# B165X.net
KiCad netlist of a schematic drawn in EAGLE
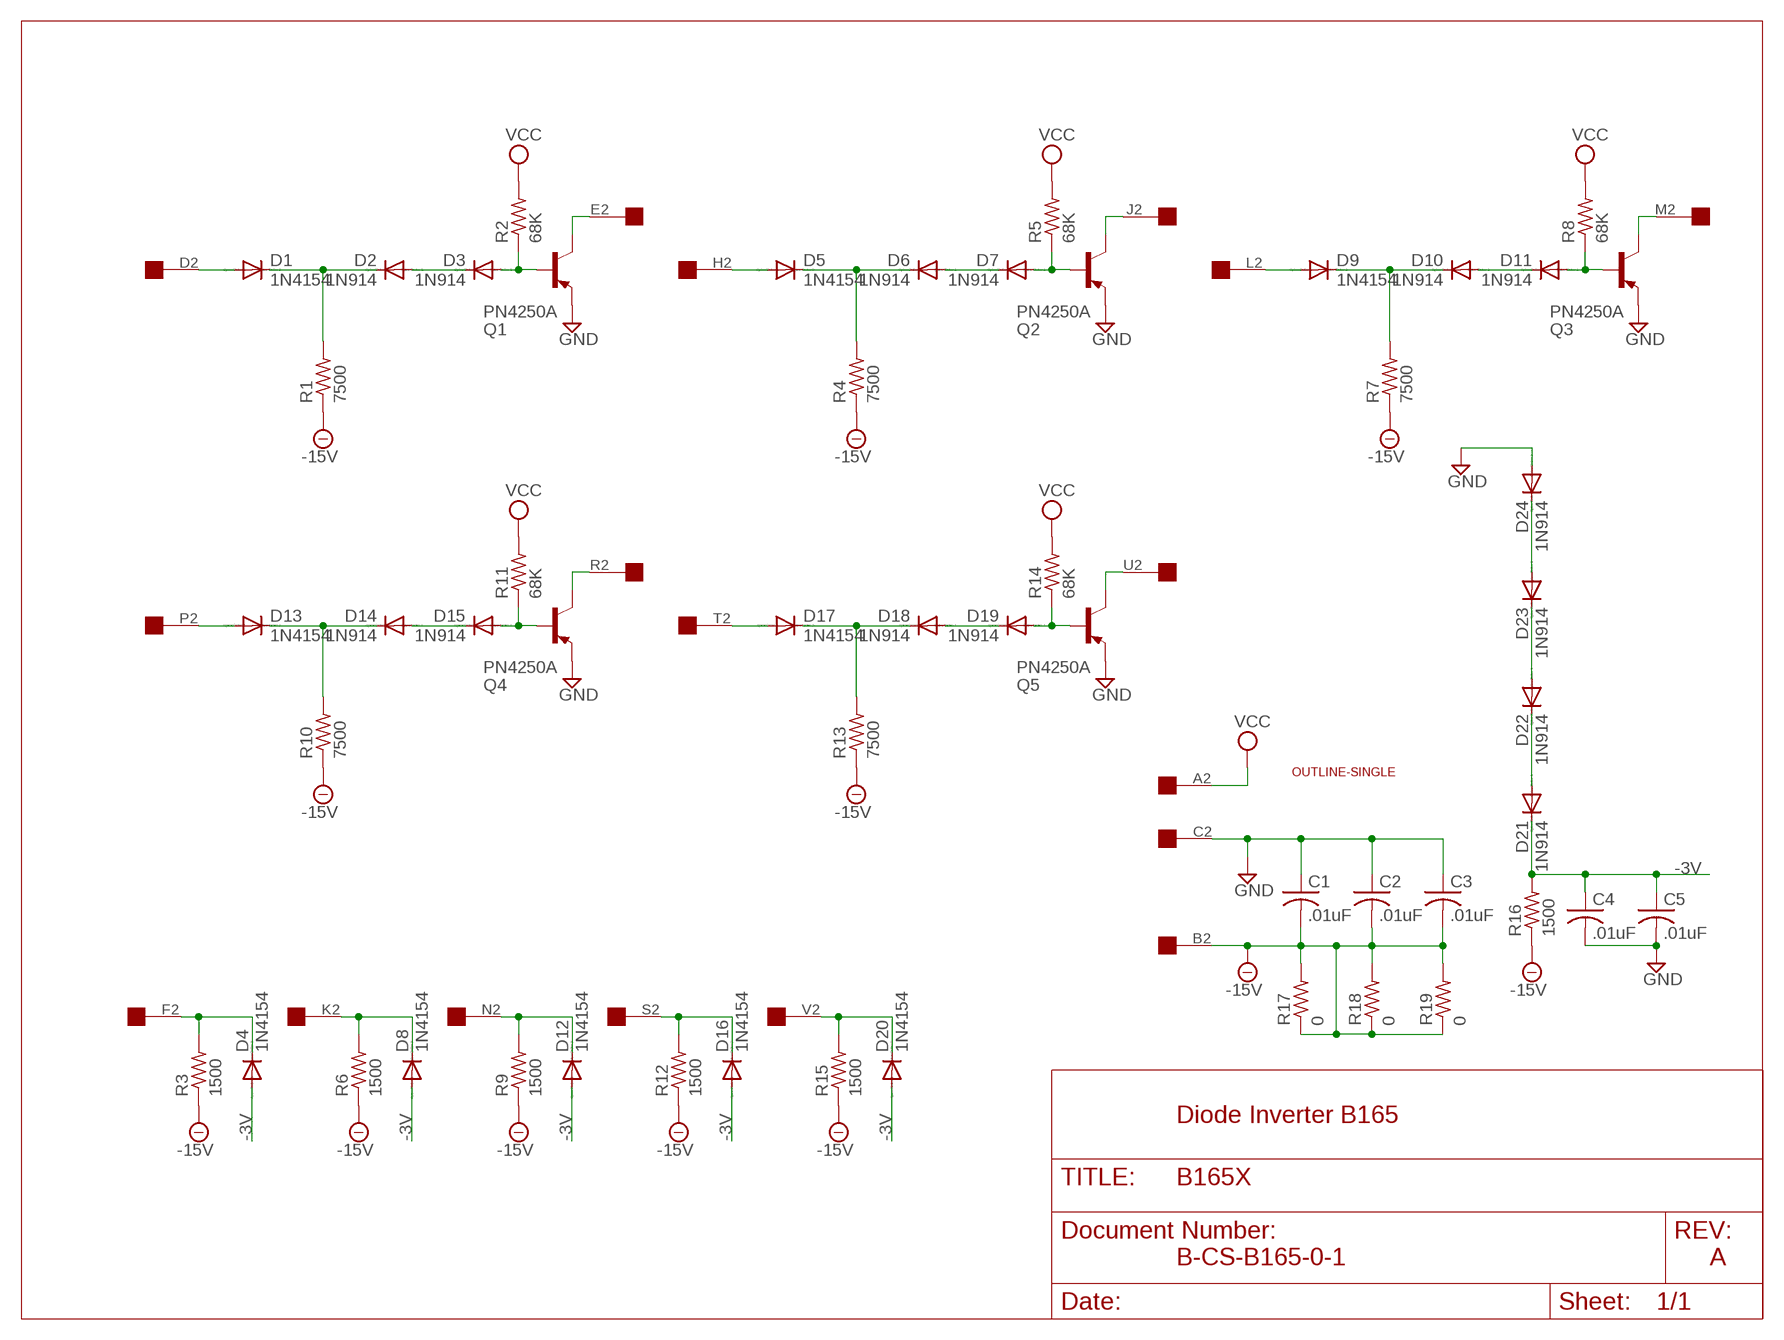
[diagram p0: schematic, sheet 1]

(export (version "E")
  (design (tool "Eeschema 10.0.6"))
  (components
    (comp (ref "C1")
      (value ".01uF")
      (footprint "eagle-import:C063-025X075")
      (libsource (lib "eagle-import") (part "C-US"))
    )
    (comp (ref "C2")
      (value ".01uF")
      (footprint "eagle-import:C063-025X075")
      (libsource (lib "eagle-import") (part "C-US"))
    )
    (comp (ref "C3")
      (value ".01uF")
      (footprint "eagle-import:C063-025X075")
      (libsource (lib "eagle-import") (part "C-US"))
    )
    (comp (ref "C4")
      (value ".01uF")
      (footprint "eagle-import:C063-025X075")
      (libsource (lib "eagle-import") (part "C-US"))
    )
    (comp (ref "C5")
      (value ".01uF")
      (footprint "eagle-import:C063-025X075")
      (libsource (lib "eagle-import") (part "C-US"))
    )
    (comp (ref "D1")
      (value "1N4154")
      (footprint "eagle-import:DO35-10")
      (libsource (lib "eagle-import") (part "DIODE-DO35-10"))
    )
    (comp (ref "D2")
      (value "1N914")
      (footprint "eagle-import:DO35-10")
      (libsource (lib "eagle-import") (part "DIODE-DO35-10"))
    )
    (comp (ref "D3")
      (value "1N914")
      (footprint "eagle-import:DO35-10")
      (libsource (lib "eagle-import") (part "DIODE-DO35-10"))
    )
    (comp (ref "D4")
      (value "1N4154")
      (footprint "eagle-import:DO35-10")
      (libsource (lib "eagle-import") (part "DIODE-DO35-10"))
    )
    (comp (ref "D5")
      (value "1N4154")
      (footprint "eagle-import:DO35-10")
      (libsource (lib "eagle-import") (part "DIODE-DO35-10"))
    )
    (comp (ref "D6")
      (value "1N914")
      (footprint "eagle-import:DO35-10")
      (libsource (lib "eagle-import") (part "DIODE-DO35-10"))
    )
    (comp (ref "D7")
      (value "1N914")
      (footprint "eagle-import:DO35-10")
      (libsource (lib "eagle-import") (part "DIODE-DO35-10"))
    )
    (comp (ref "D8")
      (value "1N4154")
      (footprint "eagle-import:DO35-10")
      (libsource (lib "eagle-import") (part "DIODE-DO35-10"))
    )
    (comp (ref "D9")
      (value "1N4154")
      (footprint "eagle-import:DO35-10")
      (libsource (lib "eagle-import") (part "DIODE-DO35-10"))
    )
    (comp (ref "D10")
      (value "1N914")
      (footprint "eagle-import:DO35-10")
      (libsource (lib "eagle-import") (part "DIODE-DO35-10"))
    )
    (comp (ref "D11")
      (value "1N914")
      (footprint "eagle-import:DO35-10")
      (libsource (lib "eagle-import") (part "DIODE-DO35-10"))
    )
    (comp (ref "D12")
      (value "1N4154")
      (footprint "eagle-import:DO35-10")
      (libsource (lib "eagle-import") (part "DIODE-DO35-10"))
    )
    (comp (ref "D13")
      (value "1N4154")
      (footprint "eagle-import:DO35-10")
      (libsource (lib "eagle-import") (part "DIODE-DO35-10"))
    )
    (comp (ref "D14")
      (value "1N914")
      (footprint "eagle-import:DO35-10")
      (libsource (lib "eagle-import") (part "DIODE-DO35-10"))
    )
    (comp (ref "D15")
      (value "1N914")
      (footprint "eagle-import:DO35-10")
      (libsource (lib "eagle-import") (part "DIODE-DO35-10"))
    )
    (comp (ref "D16")
      (value "1N4154")
      (footprint "eagle-import:DO35-10")
      (libsource (lib "eagle-import") (part "DIODE-DO35-10"))
    )
    (comp (ref "D17")
      (value "1N4154")
      (footprint "eagle-import:DO35-10")
      (libsource (lib "eagle-import") (part "DIODE-DO35-10"))
    )
    (comp (ref "D18")
      (value "1N914")
      (footprint "eagle-import:DO35-10")
      (libsource (lib "eagle-import") (part "DIODE-DO35-10"))
    )
    (comp (ref "D19")
      (value "1N914")
      (footprint "eagle-import:DO35-10")
      (libsource (lib "eagle-import") (part "DIODE-DO35-10"))
    )
    (comp (ref "D20")
      (value "1N4154")
      (footprint "eagle-import:DO35-10")
      (libsource (lib "eagle-import") (part "DIODE-DO35-10"))
    )
    (comp (ref "D21")
      (value "1N914")
      (footprint "eagle-import:DO35-10")
      (libsource (lib "eagle-import") (part "DIODE-DO35-10"))
    )
    (comp (ref "D22")
      (value "1N914")
      (footprint "eagle-import:DO35-10")
      (libsource (lib "eagle-import") (part "DIODE-DO35-10"))
    )
    (comp (ref "D23")
      (value "1N914")
      (footprint "eagle-import:DO35-10")
      (libsource (lib "eagle-import") (part "DIODE-DO35-10"))
    )
    (comp (ref "D24")
      (value "1N914")
      (footprint "eagle-import:DO35-10")
      (libsource (lib "eagle-import") (part "DIODE-DO35-10"))
    )
    (comp (ref "Q1")
      (value "PN4250A")
      (footprint "eagle-import:TO5")
      (libsource (lib "eagle-import") (part "-PNP-TO5"))
    )
    (comp (ref "Q2")
      (value "PN4250A")
      (footprint "eagle-import:TO5")
      (libsource (lib "eagle-import") (part "-PNP-TO5"))
    )
    (comp (ref "Q3")
      (value "PN4250A")
      (footprint "eagle-import:TO5")
      (libsource (lib "eagle-import") (part "-PNP-TO5"))
    )
    (comp (ref "Q4")
      (value "PN4250A")
      (footprint "eagle-import:TO5")
      (libsource (lib "eagle-import") (part "-PNP-TO5"))
    )
    (comp (ref "Q5")
      (value "PN4250A")
      (footprint "eagle-import:TO5")
      (libsource (lib "eagle-import") (part "-PNP-TO5"))
    )
    (comp (ref "R1")
      (value "7500")
      (footprint "eagle-import:0207_10")
      (libsource (lib "eagle-import") (part "R-US_0207/10"))
    )
    (comp (ref "R2")
      (value "68K")
      (footprint "eagle-import:0207_10")
      (libsource (lib "eagle-import") (part "R-US_0207/10"))
    )
    (comp (ref "R3")
      (value "1500")
      (footprint "eagle-import:0207_10")
      (libsource (lib "eagle-import") (part "R-US_0207/10"))
    )
    (comp (ref "R4")
      (value "7500")
      (footprint "eagle-import:0207_10")
      (libsource (lib "eagle-import") (part "R-US_0207/10"))
    )
    (comp (ref "R5")
      (value "68K")
      (footprint "eagle-import:0207_10")
      (libsource (lib "eagle-import") (part "R-US_0207/10"))
    )
    (comp (ref "R6")
      (value "1500")
      (footprint "eagle-import:0207_10")
      (libsource (lib "eagle-import") (part "R-US_0207/10"))
    )
    (comp (ref "R7")
      (value "7500")
      (footprint "eagle-import:0207_10")
      (libsource (lib "eagle-import") (part "R-US_0207/10"))
    )
    (comp (ref "R8")
      (value "68K")
      (footprint "eagle-import:0207_10")
      (libsource (lib "eagle-import") (part "R-US_0207/10"))
    )
    (comp (ref "R9")
      (value "1500")
      (footprint "eagle-import:0207_10")
      (libsource (lib "eagle-import") (part "R-US_0207/10"))
    )
    (comp (ref "R10")
      (value "7500")
      (footprint "eagle-import:0207_10")
      (libsource (lib "eagle-import") (part "R-US_0207/10"))
    )
    (comp (ref "R11")
      (value "68K")
      (footprint "eagle-import:0207_10")
      (libsource (lib "eagle-import") (part "R-US_0207/10"))
    )
    (comp (ref "R12")
      (value "1500")
      (footprint "eagle-import:0207_10")
      (libsource (lib "eagle-import") (part "R-US_0207/10"))
    )
    (comp (ref "R13")
      (value "7500")
      (footprint "eagle-import:0207_10")
      (libsource (lib "eagle-import") (part "R-US_0207/10"))
    )
    (comp (ref "R14")
      (value "68K")
      (footprint "eagle-import:0207_10")
      (libsource (lib "eagle-import") (part "R-US_0207/10"))
    )
    (comp (ref "R15")
      (value "1500")
      (footprint "eagle-import:0207_10")
      (libsource (lib "eagle-import") (part "R-US_0207/10"))
    )
    (comp (ref "R16")
      (value "1500")
      (footprint "eagle-import:0207_10")
      (libsource (lib "eagle-import") (part "R-US_0207/10"))
    )
    (comp (ref "R17")
      (value "0")
      (footprint "eagle-import:0207_10")
      (libsource (lib "eagle-import") (part "R-US_0207/10"))
    )
    (comp (ref "R18")
      (value "0")
      (footprint "eagle-import:0207_10")
      (libsource (lib "eagle-import") (part "R-US_0207/10"))
    )
    (comp (ref "R19")
      (value "0")
      (footprint "eagle-import:0207_10")
      (libsource (lib "eagle-import") (part "R-US_0207/10"))
    )
    (comp (ref "U$1")
      (value "OUTLINE-SINGLE")
      (footprint "eagle-import:SINGLE")
      (libsource (lib "eagle-import") (part "OUTLINE-SINGLE"))
    )
    (comp (ref "U$2")
      (value "EDGE-1")
      (footprint "eagle-import:EDGE-CON1")
      (libsource (lib "eagle-import") (part "EDGE-1"))
    )
  )
  (nets
    (net (code "1") (name "-15V") (class "Default")
      (node (ref "C1") (pin "2") (pinfunction "2_2") (pintype "passive"))
      (node (ref "C2") (pin "2") (pinfunction "2_2") (pintype "passive"))
      (node (ref "C3") (pin "2") (pinfunction "2_2") (pintype "passive"))
      (node (ref "R1") (pin "1") (pinfunction "1_1") (pintype "passive"))
      (node (ref "R10") (pin "1") (pinfunction "1_1") (pintype "passive"))
      (node (ref "R12") (pin "1") (pinfunction "1_1") (pintype "passive"))
      (node (ref "R13") (pin "1") (pinfunction "1_1") (pintype "passive"))
      (node (ref "R15") (pin "1") (pinfunction "1_1") (pintype "passive"))
      (node (ref "R16") (pin "1") (pinfunction "1_1") (pintype "passive"))
      (node (ref "R17") (pin "1") (pinfunction "1_1") (pintype "passive"))
      (node (ref "R17") (pin "2") (pinfunction "2_2") (pintype "passive"))
      (node (ref "R18") (pin "1") (pinfunction "1_1") (pintype "passive"))
      (node (ref "R18") (pin "2") (pinfunction "2_2") (pintype "passive"))
      (node (ref "R19") (pin "1") (pinfunction "1_1") (pintype "passive"))
      (node (ref "R19") (pin "2") (pinfunction "2_2") (pintype "passive"))
      (node (ref "R3") (pin "1") (pinfunction "1_1") (pintype "passive"))
      (node (ref "R4") (pin "1") (pinfunction "1_1") (pintype "passive"))
      (node (ref "R6") (pin "1") (pinfunction "1_1") (pintype "passive"))
      (node (ref "R7") (pin "1") (pinfunction "1_1") (pintype "passive"))
      (node (ref "R9") (pin "1") (pinfunction "1_1") (pintype "passive"))
      (node (ref "U$2") (pin "B2") (pinfunction "1_B2") (pintype "bidirectional"))
    )
    (net (code "2") (name "/-3V") (class "Default")
      (node (ref "C4") (pin "1") (pinfunction "1_1") (pintype "passive"))
      (node (ref "C5") (pin "1") (pinfunction "1_1") (pintype "passive"))
      (node (ref "D12") (pin "A") (pinfunction "A_A") (pintype "passive"))
      (node (ref "D16") (pin "A") (pinfunction "A_A") (pintype "passive"))
      (node (ref "D20") (pin "A") (pinfunction "A_A") (pintype "passive"))
      (node (ref "D21") (pin "C") (pinfunction "C_C") (pintype "passive"))
      (node (ref "D4") (pin "A") (pinfunction "A_A") (pintype "passive"))
      (node (ref "D8") (pin "A") (pinfunction "A_A") (pintype "passive"))
      (node (ref "R16") (pin "2") (pinfunction "2_2") (pintype "passive"))
    )
    (net (code "3") (name "GND") (class "Default")
      (node (ref "C1") (pin "1") (pinfunction "1_1") (pintype "passive"))
      (node (ref "C2") (pin "1") (pinfunction "1_1") (pintype "passive"))
      (node (ref "C3") (pin "1") (pinfunction "1_1") (pintype "passive"))
      (node (ref "C4") (pin "2") (pinfunction "2_2") (pintype "passive"))
      (node (ref "C5") (pin "2") (pinfunction "2_2") (pintype "passive"))
      (node (ref "D24") (pin "A") (pinfunction "A_A") (pintype "passive"))
      (node (ref "Q1") (pin "1") (pinfunction "E_1") (pintype "passive"))
      (node (ref "Q2") (pin "1") (pinfunction "E_1") (pintype "passive"))
      (node (ref "Q3") (pin "1") (pinfunction "E_1") (pintype "passive"))
      (node (ref "Q4") (pin "1") (pinfunction "E_1") (pintype "passive"))
      (node (ref "Q5") (pin "1") (pinfunction "E_1") (pintype "passive"))
      (node (ref "U$2") (pin "C2") (pinfunction "1_C2") (pintype "bidirectional"))
    )
    (net (code "4") (name "Net-(D1-PadC)") (class "Default")
      (node (ref "D1") (pin "C") (pinfunction "C_C") (pintype "passive"))
      (node (ref "D2") (pin "C") (pinfunction "C_C") (pintype "passive"))
      (node (ref "R1") (pin "2") (pinfunction "2_2") (pintype "passive"))
    )
    (net (code "5") (name "Net-(D2-PadA)") (class "Default")
      (node (ref "D2") (pin "A") (pinfunction "A_A") (pintype "passive"))
      (node (ref "D3") (pin "C") (pinfunction "C_C") (pintype "passive"))
    )
    (net (code "6") (name "Net-(D5-PadC)") (class "Default")
      (node (ref "D5") (pin "C") (pinfunction "C_C") (pintype "passive"))
      (node (ref "D6") (pin "C") (pinfunction "C_C") (pintype "passive"))
      (node (ref "R4") (pin "2") (pinfunction "2_2") (pintype "passive"))
    )
    (net (code "7") (name "Net-(D6-PadA)") (class "Default")
      (node (ref "D6") (pin "A") (pinfunction "A_A") (pintype "passive"))
      (node (ref "D7") (pin "C") (pinfunction "C_C") (pintype "passive"))
    )
    (net (code "8") (name "Net-(D10-PadA)") (class "Default")
      (node (ref "D10") (pin "A") (pinfunction "A_A") (pintype "passive"))
      (node (ref "D11") (pin "C") (pinfunction "C_C") (pintype "passive"))
    )
    (net (code "9") (name "Net-(D10-PadC)") (class "Default")
      (node (ref "D10") (pin "C") (pinfunction "C_C") (pintype "passive"))
      (node (ref "D9") (pin "C") (pinfunction "C_C") (pintype "passive"))
      (node (ref "R7") (pin "2") (pinfunction "2_2") (pintype "passive"))
    )
    (net (code "10") (name "Net-(D13-PadC)") (class "Default")
      (node (ref "D13") (pin "C") (pinfunction "C_C") (pintype "passive"))
      (node (ref "D14") (pin "C") (pinfunction "C_C") (pintype "passive"))
      (node (ref "R10") (pin "2") (pinfunction "2_2") (pintype "passive"))
    )
    (net (code "11") (name "Net-(D14-PadA)") (class "Default")
      (node (ref "D14") (pin "A") (pinfunction "A_A") (pintype "passive"))
      (node (ref "D15") (pin "C") (pinfunction "C_C") (pintype "passive"))
    )
    (net (code "12") (name "Net-(D17-PadC)") (class "Default")
      (node (ref "D17") (pin "C") (pinfunction "C_C") (pintype "passive"))
      (node (ref "D18") (pin "C") (pinfunction "C_C") (pintype "passive"))
      (node (ref "R13") (pin "2") (pinfunction "2_2") (pintype "passive"))
    )
    (net (code "13") (name "Net-(D18-PadA)") (class "Default")
      (node (ref "D18") (pin "A") (pinfunction "A_A") (pintype "passive"))
      (node (ref "D19") (pin "C") (pinfunction "C_C") (pintype "passive"))
    )
    (net (code "14") (name "Net-(D21-PadA)") (class "Default")
      (node (ref "D21") (pin "A") (pinfunction "A_A") (pintype "passive"))
      (node (ref "D22") (pin "C") (pinfunction "C_C") (pintype "passive"))
    )
    (net (code "15") (name "Net-(D22-PadA)") (class "Default")
      (node (ref "D22") (pin "A") (pinfunction "A_A") (pintype "passive"))
      (node (ref "D23") (pin "C") (pinfunction "C_C") (pintype "passive"))
    )
    (net (code "16") (name "Net-(D23-PadA)") (class "Default")
      (node (ref "D23") (pin "A") (pinfunction "A_A") (pintype "passive"))
      (node (ref "D24") (pin "C") (pinfunction "C_C") (pintype "passive"))
    )
    (net (code "17") (name "Net-(Q1-B)") (class "Default")
      (node (ref "D3") (pin "A") (pinfunction "A_A") (pintype "passive"))
      (node (ref "Q1") (pin "2") (pinfunction "B_2") (pintype "passive"))
      (node (ref "R2") (pin "1") (pinfunction "1_1") (pintype "passive"))
    )
    (net (code "18") (name "Net-(Q1-C)") (class "Default")
      (node (ref "Q1") (pin "3") (pinfunction "C_3") (pintype "passive"))
      (node (ref "U$2") (pin "E2") (pinfunction "1_E2") (pintype "bidirectional"))
    )
    (net (code "19") (name "Net-(Q2-B)") (class "Default")
      (node (ref "D7") (pin "A") (pinfunction "A_A") (pintype "passive"))
      (node (ref "Q2") (pin "2") (pinfunction "B_2") (pintype "passive"))
      (node (ref "R5") (pin "1") (pinfunction "1_1") (pintype "passive"))
    )
    (net (code "20") (name "Net-(Q2-C)") (class "Default")
      (node (ref "Q2") (pin "3") (pinfunction "C_3") (pintype "passive"))
      (node (ref "U$2") (pin "J2") (pinfunction "1_J2") (pintype "bidirectional"))
    )
    (net (code "21") (name "Net-(Q3-B)") (class "Default")
      (node (ref "D11") (pin "A") (pinfunction "A_A") (pintype "passive"))
      (node (ref "Q3") (pin "2") (pinfunction "B_2") (pintype "passive"))
      (node (ref "R8") (pin "1") (pinfunction "1_1") (pintype "passive"))
    )
    (net (code "22") (name "Net-(Q3-C)") (class "Default")
      (node (ref "Q3") (pin "3") (pinfunction "C_3") (pintype "passive"))
      (node (ref "U$2") (pin "M2") (pinfunction "1_M2") (pintype "bidirectional"))
    )
    (net (code "23") (name "Net-(Q4-B)") (class "Default")
      (node (ref "D15") (pin "A") (pinfunction "A_A") (pintype "passive"))
      (node (ref "Q4") (pin "2") (pinfunction "B_2") (pintype "passive"))
      (node (ref "R11") (pin "1") (pinfunction "1_1") (pintype "passive"))
    )
    (net (code "24") (name "Net-(Q4-C)") (class "Default")
      (node (ref "Q4") (pin "3") (pinfunction "C_3") (pintype "passive"))
      (node (ref "U$2") (pin "R2") (pinfunction "1_R2") (pintype "bidirectional"))
    )
    (net (code "25") (name "Net-(Q5-B)") (class "Default")
      (node (ref "D19") (pin "A") (pinfunction "A_A") (pintype "passive"))
      (node (ref "Q5") (pin "2") (pinfunction "B_2") (pintype "passive"))
      (node (ref "R14") (pin "1") (pinfunction "1_1") (pintype "passive"))
    )
    (net (code "26") (name "Net-(Q5-C)") (class "Default")
      (node (ref "Q5") (pin "3") (pinfunction "C_3") (pintype "passive"))
      (node (ref "U$2") (pin "U2") (pinfunction "1_U2") (pintype "bidirectional"))
    )
    (net (code "27") (name "Net-(U$2D-1)") (class "Default")
      (node (ref "D1") (pin "A") (pinfunction "A_A") (pintype "passive"))
      (node (ref "U$2") (pin "D2") (pinfunction "1_D2") (pintype "bidirectional"))
    )
    (net (code "28") (name "Net-(U$2F-1)") (class "Default")
      (node (ref "D4") (pin "C") (pinfunction "C_C") (pintype "passive"))
      (node (ref "R3") (pin "2") (pinfunction "2_2") (pintype "passive"))
      (node (ref "U$2") (pin "F2") (pinfunction "1_F2") (pintype "bidirectional"))
    )
    (net (code "29") (name "Net-(U$2G-1)") (class "Default")
      (node (ref "D5") (pin "A") (pinfunction "A_A") (pintype "passive"))
      (node (ref "U$2") (pin "H2") (pinfunction "1_H2") (pintype "bidirectional"))
    )
    (net (code "30") (name "Net-(U$2I-1)") (class "Default")
      (node (ref "D8") (pin "C") (pinfunction "C_C") (pintype "passive"))
      (node (ref "R6") (pin "2") (pinfunction "2_2") (pintype "passive"))
      (node (ref "U$2") (pin "K2") (pinfunction "1_K2") (pintype "bidirectional"))
    )
    (net (code "31") (name "Net-(U$2J-1)") (class "Default")
      (node (ref "D9") (pin "A") (pinfunction "A_A") (pintype "passive"))
      (node (ref "U$2") (pin "L2") (pinfunction "1_L2") (pintype "bidirectional"))
    )
    (net (code "32") (name "Net-(U$2L-1)") (class "Default")
      (node (ref "D12") (pin "C") (pinfunction "C_C") (pintype "passive"))
      (node (ref "R9") (pin "2") (pinfunction "2_2") (pintype "passive"))
      (node (ref "U$2") (pin "N2") (pinfunction "1_N2") (pintype "bidirectional"))
    )
    (net (code "33") (name "Net-(U$2M-1)") (class "Default")
      (node (ref "D13") (pin "A") (pinfunction "A_A") (pintype "passive"))
      (node (ref "U$2") (pin "P2") (pinfunction "1_P2") (pintype "bidirectional"))
    )
    (net (code "34") (name "Net-(U$2O-1)") (class "Default")
      (node (ref "D16") (pin "C") (pinfunction "C_C") (pintype "passive"))
      (node (ref "R12") (pin "2") (pinfunction "2_2") (pintype "passive"))
      (node (ref "U$2") (pin "S2") (pinfunction "1_S2") (pintype "bidirectional"))
    )
    (net (code "35") (name "Net-(U$2P-1)") (class "Default")
      (node (ref "D17") (pin "A") (pinfunction "A_A") (pintype "passive"))
      (node (ref "U$2") (pin "T2") (pinfunction "1_T2") (pintype "bidirectional"))
    )
    (net (code "36") (name "Net-(U$2R-1)") (class "Default")
      (node (ref "D20") (pin "C") (pinfunction "C_C") (pintype "passive"))
      (node (ref "R15") (pin "2") (pinfunction "2_2") (pintype "passive"))
      (node (ref "U$2") (pin "V2") (pinfunction "1_V2") (pintype "bidirectional"))
    )
    (net (code "37") (name "VCC") (class "Default")
      (node (ref "R11") (pin "2") (pinfunction "2_2") (pintype "passive"))
      (node (ref "R14") (pin "2") (pinfunction "2_2") (pintype "passive"))
      (node (ref "R2") (pin "2") (pinfunction "2_2") (pintype "passive"))
      (node (ref "R5") (pin "2") (pinfunction "2_2") (pintype "passive"))
      (node (ref "R8") (pin "2") (pinfunction "2_2") (pintype "passive"))
      (node (ref "U$2") (pin "A2") (pinfunction "1_A2") (pintype "bidirectional"))
    )
  )
)
